# blds.net
KiCad netlist of a schematic drawn in Altium Designer
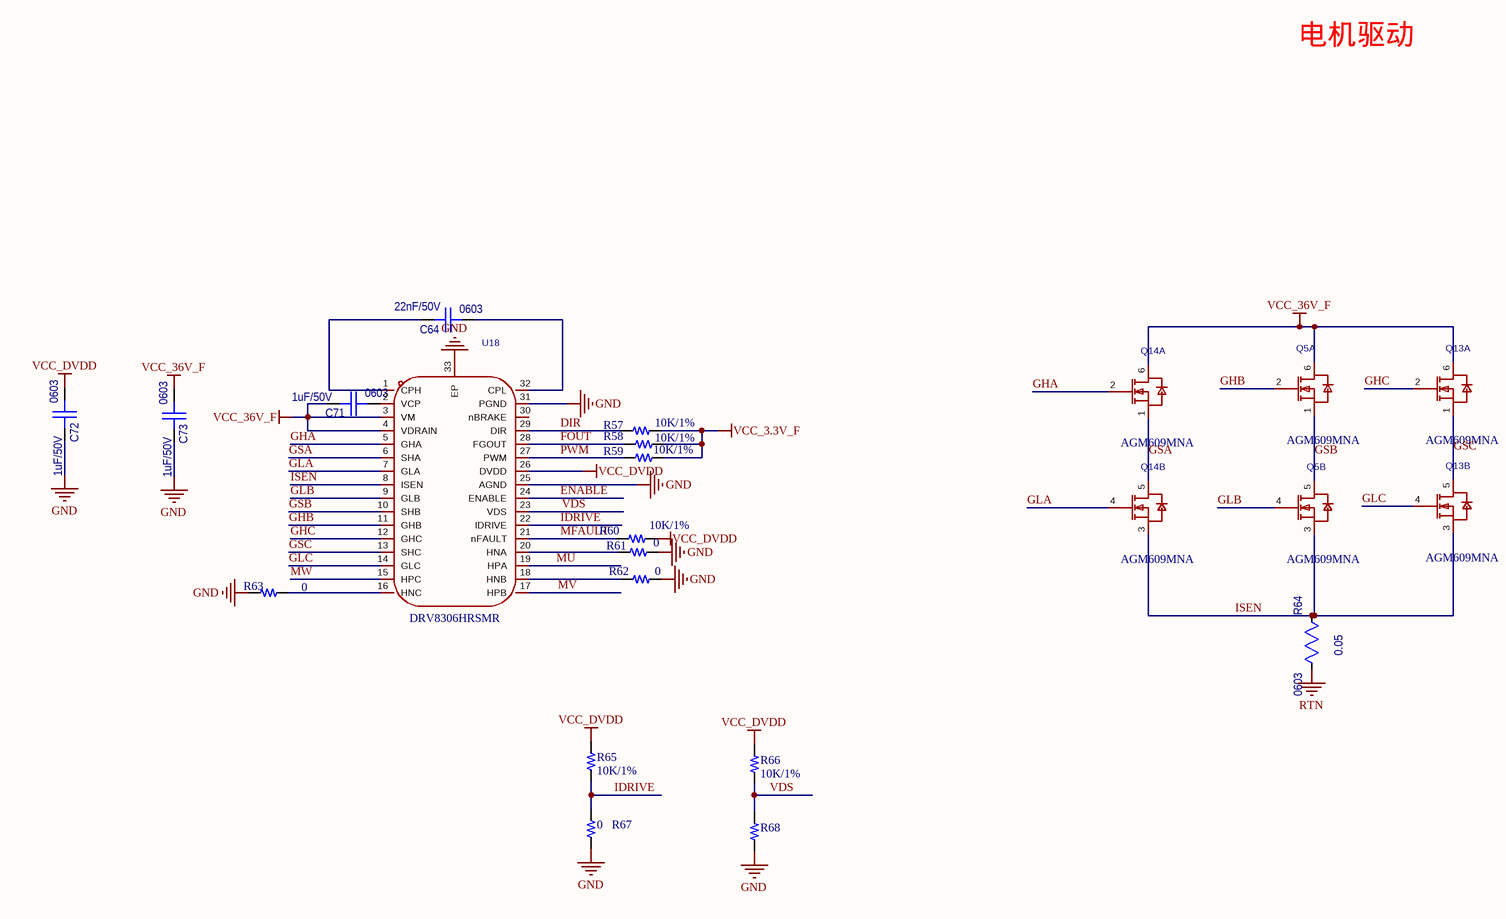
[diagram p0: blds.SchDoc]

(export (version "E")
  (design (tool "Eeschema 10.0.6"))
  (components
    (comp (ref "C64")
      (value "22nF/50V")
      (footprint "CAPC1608X092N_0603")
      (description "Capacitor, MLCC")
      (fields
        (field (name "MANUFACTURER") "muRata")
        (field (name "PARTNUMBER") "GQM2195C2E4R7CB12J")
        (field (name "PACKAGE") "0603")
      )
      (libsource (lib "Karl") (part "Capacitor_0603"))
    )
    (comp (ref "C71")
      (value "1uF/50V")
      (footprint "CAPC1608X092N_0603")
      (description "Capacitor, MLCC")
      (fields
        (field (name "MANUFACTURER") "muRata")
        (field (name "PARTNUMBER") "GQM2195C2E4R7CB12J")
        (field (name "PACKAGE") "0603")
      )
      (libsource (lib "Karl") (part "Capacitor_0603"))
    )
    (comp (ref "C72")
      (value "1uF/50V")
      (footprint "CAPC1608X092N_0603")
      (description "Capacitor, MLCC")
      (fields
        (field (name "MANUFACTURER") "muRata")
        (field (name "PARTNUMBER") "GQM2195C2E4R7CB12J")
        (field (name "PACKAGE") "0603")
      )
      (libsource (lib "Karl") (part "Capacitor_0603"))
    )
    (comp (ref "C73")
      (value "1uF/50V")
      (footprint "CAPC1608X092N_0603")
      (description "Capacitor, MLCC")
      (fields
        (field (name "MANUFACTURER") "muRata")
        (field (name "PARTNUMBER") "GQM2195C2E4R7CB12J")
        (field (name "PACKAGE") "0603")
      )
      (libsource (lib "Karl") (part "Capacitor_0603"))
    )
    (comp (ref "Q5")
      (value "AGM609MNA")
      (footprint "DFN-8_L5.5-W5.2-P1.27-LS6.0-BL-EP2")
      (libsource (lib "altium-import") (part "root_0_AGM609MNA_"))
    )
    (comp (ref "Q13")
      (value "AGM609MNA")
      (footprint "DFN-8_L5.5-W5.2-P1.27-LS6.0-BL-EP2")
      (libsource (lib "altium-import") (part "root_0_AGM609MNA_"))
    )
    (comp (ref "Q14")
      (value "AGM609MNA")
      (footprint "DFN-8_L5.5-W5.2-P1.27-LS6.0-BL-EP2")
      (libsource (lib "altium-import") (part "root_0_AGM609MNA_"))
    )
    (comp (ref "R57") (value "10K/1%") (footprint "0603R") (libsource (lib "JRJ_1") (part "R")))
    (comp (ref "R58") (value "10K/1%") (footprint "0603R") (libsource (lib "JRJ_1") (part "R")))
    (comp (ref "R59") (value "10K/1%") (footprint "0603R") (libsource (lib "JRJ_1") (part "R")))
    (comp (ref "R60") (value "10K/1%") (footprint "0603R") (libsource (lib "JRJ_1") (part "R")))
    (comp (ref "R61") (value "0") (footprint "0603R") (libsource (lib "JRJ_1") (part "R")))
    (comp (ref "R62") (value "0") (footprint "0603R") (libsource (lib "JRJ_1") (part "R")))
    (comp (ref "R63") (value "0") (footprint "0603R") (libsource (lib "JRJ_1") (part "R")))
    (comp (ref "R64")
      (value "0.05")
      (footprint "2010R")
      (description "Resistor, Standard")
      (fields
        (field (name "MANUFACTURER") "Yageo")
        (field (name "PARTNUMBER") "RC0603FR-0710KL")
        (field (name "PACKAGE") "0603")
      )
      (libsource (lib "Karl") (part "Resistor_0603"))
    )
    (comp (ref "R65") (value "10K/1%") (footprint "0603R") (libsource (lib "JRJ_1") (part "R")))
    (comp (ref "R66") (value "10K/1%") (footprint "0603R") (libsource (lib "JRJ_1") (part "R")))
    (comp (ref "R67") (value "0") (footprint "0603R") (libsource (lib "JRJ_1") (part "R")))
    (comp (ref "R68") (value "0") (footprint "0603R") (libsource (lib "JRJ_1") (part "R")))
    (comp (ref "U18")
      (value "DRV8306HRSMR")
      (footprint "VQFN-32_L4.0-W4.0-P0.40-BL-EP")
      (libsource (lib "altium-import") (part "root_0_DRV8306HRSMR_"))
    )
  )
  (nets
    (net (code "1") (name "/DIR") (class "Default")
      (node (ref "R57") (pin "1") (pintype "passive"))
      (node (ref "U18") (pin "29") (pinfunction "DIR_29") (pintype "passive"))
    )
    (net (code "2") (name "/ENABLE") (class "Default")
      (node (ref "U18") (pin "24") (pinfunction "ENABLE_24") (pintype "passive"))
    )
    (net (code "3") (name "/FOUT") (class "Default")
      (node (ref "R58") (pin "1") (pintype "passive"))
      (node (ref "U18") (pin "28") (pinfunction "FGOUT_28") (pintype "passive"))
    )
    (net (code "4") (name "/GHA") (class "Default")
      (node (ref "Q14") (pin "2") (pinfunction "G1_2") (pintype "passive"))
      (node (ref "U18") (pin "5") (pinfunction "GHA_5") (pintype "passive"))
    )
    (net (code "5") (name "/GHB") (class "Default")
      (node (ref "Q5") (pin "2") (pinfunction "G1_2") (pintype "passive"))
      (node (ref "U18") (pin "11") (pinfunction "GHB_11") (pintype "passive"))
    )
    (net (code "6") (name "/GHC") (class "Default")
      (node (ref "Q13") (pin "2") (pinfunction "G1_2") (pintype "passive"))
      (node (ref "U18") (pin "12") (pinfunction "GHC_12") (pintype "passive"))
    )
    (net (code "7") (name "/GLA") (class "Default")
      (node (ref "Q14") (pin "4") (pinfunction "G2_4") (pintype "passive"))
      (node (ref "U18") (pin "7") (pinfunction "GLA_7") (pintype "passive"))
    )
    (net (code "8") (name "/GLB") (class "Default")
      (node (ref "Q5") (pin "4") (pinfunction "G2_4") (pintype "passive"))
      (node (ref "U18") (pin "9") (pinfunction "GLB_9") (pintype "passive"))
    )
    (net (code "9") (name "/GLC") (class "Default")
      (node (ref "Q13") (pin "4") (pinfunction "G2_4") (pintype "passive"))
      (node (ref "U18") (pin "14") (pinfunction "GLC_14") (pintype "passive"))
    )
    (net (code "10") (name "/GSA") (class "Default")
      (node (ref "Q14") (pin "1") (pinfunction "S1_1") (pintype "passive"))
      (node (ref "Q14") (pin "5") (pinfunction "D2_5") (pintype "passive"))
      (node (ref "U18") (pin "6") (pinfunction "SHA_6") (pintype "passive"))
    )
    (net (code "11") (name "/GSB") (class "Default")
      (node (ref "Q5") (pin "1") (pinfunction "S1_1") (pintype "passive"))
      (node (ref "Q5") (pin "5") (pinfunction "D2_5") (pintype "passive"))
      (node (ref "U18") (pin "10") (pinfunction "SHB_10") (pintype "passive"))
    )
    (net (code "12") (name "/GSC") (class "Default")
      (node (ref "Q13") (pin "1") (pinfunction "S1_1") (pintype "passive"))
      (node (ref "Q13") (pin "5") (pinfunction "D2_5") (pintype "passive"))
      (node (ref "U18") (pin "13") (pinfunction "SHC_13") (pintype "passive"))
    )
    (net (code "13") (name "/IDRIVE") (class "Default")
      (node (ref "R65") (pin "2") (pintype "passive"))
      (node (ref "R67") (pin "1") (pintype "passive"))
      (node (ref "U18") (pin "22") (pinfunction "IDRIVE_22") (pintype "passive"))
    )
    (net (code "14") (name "/ISEN") (class "Default")
      (node (ref "Q13") (pin "3") (pinfunction "S2_3") (pintype "passive"))
      (node (ref "Q14") (pin "3") (pinfunction "S2_3") (pintype "passive"))
      (node (ref "Q5") (pin "3") (pinfunction "S2_3") (pintype "passive"))
      (node (ref "R64") (pin "2") (pinfunction "2_2") (pintype "passive"))
      (node (ref "U18") (pin "8") (pinfunction "ISEN_8") (pintype "passive"))
    )
    (net (code "15") (name "/MFAULT") (class "Default")
      (node (ref "R60") (pin "1") (pintype "passive"))
      (node (ref "U18") (pin "21") (pinfunction "nFAULT_21") (pintype "passive"))
    )
    (net (code "16") (name "/MU") (class "Default")
      (node (ref "U18") (pin "19") (pinfunction "HPA_19") (pintype "passive"))
    )
    (net (code "17") (name "/MV") (class "Default")
      (node (ref "U18") (pin "17") (pinfunction "HPB_17") (pintype "passive"))
    )
    (net (code "18") (name "/MW") (class "Default")
      (node (ref "U18") (pin "15") (pinfunction "HPC_15") (pintype "passive"))
    )
    (net (code "19") (name "/PWM") (class "Default")
      (node (ref "R59") (pin "1") (pintype "passive"))
      (node (ref "U18") (pin "27") (pinfunction "PWM_27") (pintype "passive"))
    )
    (net (code "20") (name "/VDS") (class "Default")
      (node (ref "R66") (pin "2") (pintype "passive"))
      (node (ref "R68") (pin "1") (pintype "passive"))
      (node (ref "U18") (pin "23") (pinfunction "VDS_23") (pintype "passive"))
    )
    (net (code "21") (name "GND") (class "Default")
      (node (ref "C72") (pin "2") (pinfunction "2_2") (pintype "passive"))
      (node (ref "C73") (pin "2") (pinfunction "2_2") (pintype "passive"))
      (node (ref "R61") (pin "2") (pintype "passive"))
      (node (ref "R62") (pin "2") (pintype "passive"))
      (node (ref "R63") (pin "2") (pintype "passive"))
      (node (ref "R67") (pin "2") (pintype "passive"))
      (node (ref "R68") (pin "2") (pintype "passive"))
      (node (ref "U18") (pin "25") (pinfunction "AGND_25") (pintype "passive"))
      (node (ref "U18") (pin "31") (pinfunction "PGND_31") (pintype "passive"))
      (node (ref "U18") (pin "33") (pinfunction "EP_33") (pintype "passive"))
    )
    (net (code "22") (name "Net-(U18-CPH)") (class "Default")
      (node (ref "C64") (pin "2") (pinfunction "2_2") (pintype "passive"))
      (node (ref "U18") (pin "1") (pinfunction "CPH_1") (pintype "passive"))
    )
    (net (code "23") (name "Net-(U18-CPL)") (class "Default")
      (node (ref "C64") (pin "1") (pinfunction "1_1") (pintype "passive"))
      (node (ref "U18") (pin "32") (pinfunction "CPL_32") (pintype "passive"))
    )
    (net (code "24") (name "Net-(U18-HNA)") (class "Default")
      (node (ref "R61") (pin "1") (pintype "passive"))
      (node (ref "U18") (pin "20") (pinfunction "HNA_20") (pintype "passive"))
    )
    (net (code "25") (name "Net-(U18-HNB)") (class "Default")
      (node (ref "R62") (pin "1") (pintype "passive"))
      (node (ref "U18") (pin "18") (pinfunction "HNB_18") (pintype "passive"))
    )
    (net (code "26") (name "Net-(U18-HNC)") (class "Default")
      (node (ref "R63") (pin "1") (pintype "passive"))
      (node (ref "U18") (pin "16") (pinfunction "HNC_16") (pintype "passive"))
    )
    (net (code "27") (name "Net-(U18-VCP)") (class "Default")
      (node (ref "C71") (pin "1") (pinfunction "1_1") (pintype "passive"))
      (node (ref "U18") (pin "2") (pinfunction "VCP_2") (pintype "passive"))
    )
    (net (code "28") (name "RTN") (class "Default")
      (node (ref "R64") (pin "1") (pinfunction "1_1") (pintype "passive"))
    )
    (net (code "29") (name "VCC_3.3V_F") (class "Default")
      (node (ref "R57") (pin "2") (pintype "passive"))
      (node (ref "R58") (pin "2") (pintype "passive"))
      (node (ref "R59") (pin "2") (pintype "passive"))
    )
    (net (code "30") (name "VCC_36V_F") (class "Default")
      (node (ref "C71") (pin "2") (pinfunction "2_2") (pintype "passive"))
      (node (ref "C73") (pin "1") (pinfunction "1_1") (pintype "passive"))
      (node (ref "Q13") (pin "6") (pinfunction "D1_6") (pintype "passive"))
      (node (ref "Q14") (pin "6") (pinfunction "D1_6") (pintype "passive"))
      (node (ref "Q5") (pin "6") (pinfunction "D1_6") (pintype "passive"))
      (node (ref "U18") (pin "3") (pinfunction "VM_3") (pintype "passive"))
      (node (ref "U18") (pin "4") (pinfunction "VDRAIN_4") (pintype "passive"))
    )
    (net (code "31") (name "VCC_DVDD") (class "Default")
      (node (ref "C72") (pin "1") (pinfunction "1_1") (pintype "passive"))
      (node (ref "R60") (pin "2") (pintype "passive"))
      (node (ref "R65") (pin "1") (pintype "passive"))
      (node (ref "R66") (pin "1") (pintype "passive"))
      (node (ref "U18") (pin "26") (pinfunction "DVDD_26") (pintype "passive"))
    )
    (net (code "32") (name "unconnected-(U18-nBRAKE-Pad30)") (class "Default")
      (node (ref "U18") (pin "30") (pinfunction "nBRAKE_30") (pintype "passive"))
    )
  )
)
